# MarazLiteKumanda.net
KiCad netlist of a schematic drawn in EAGLE
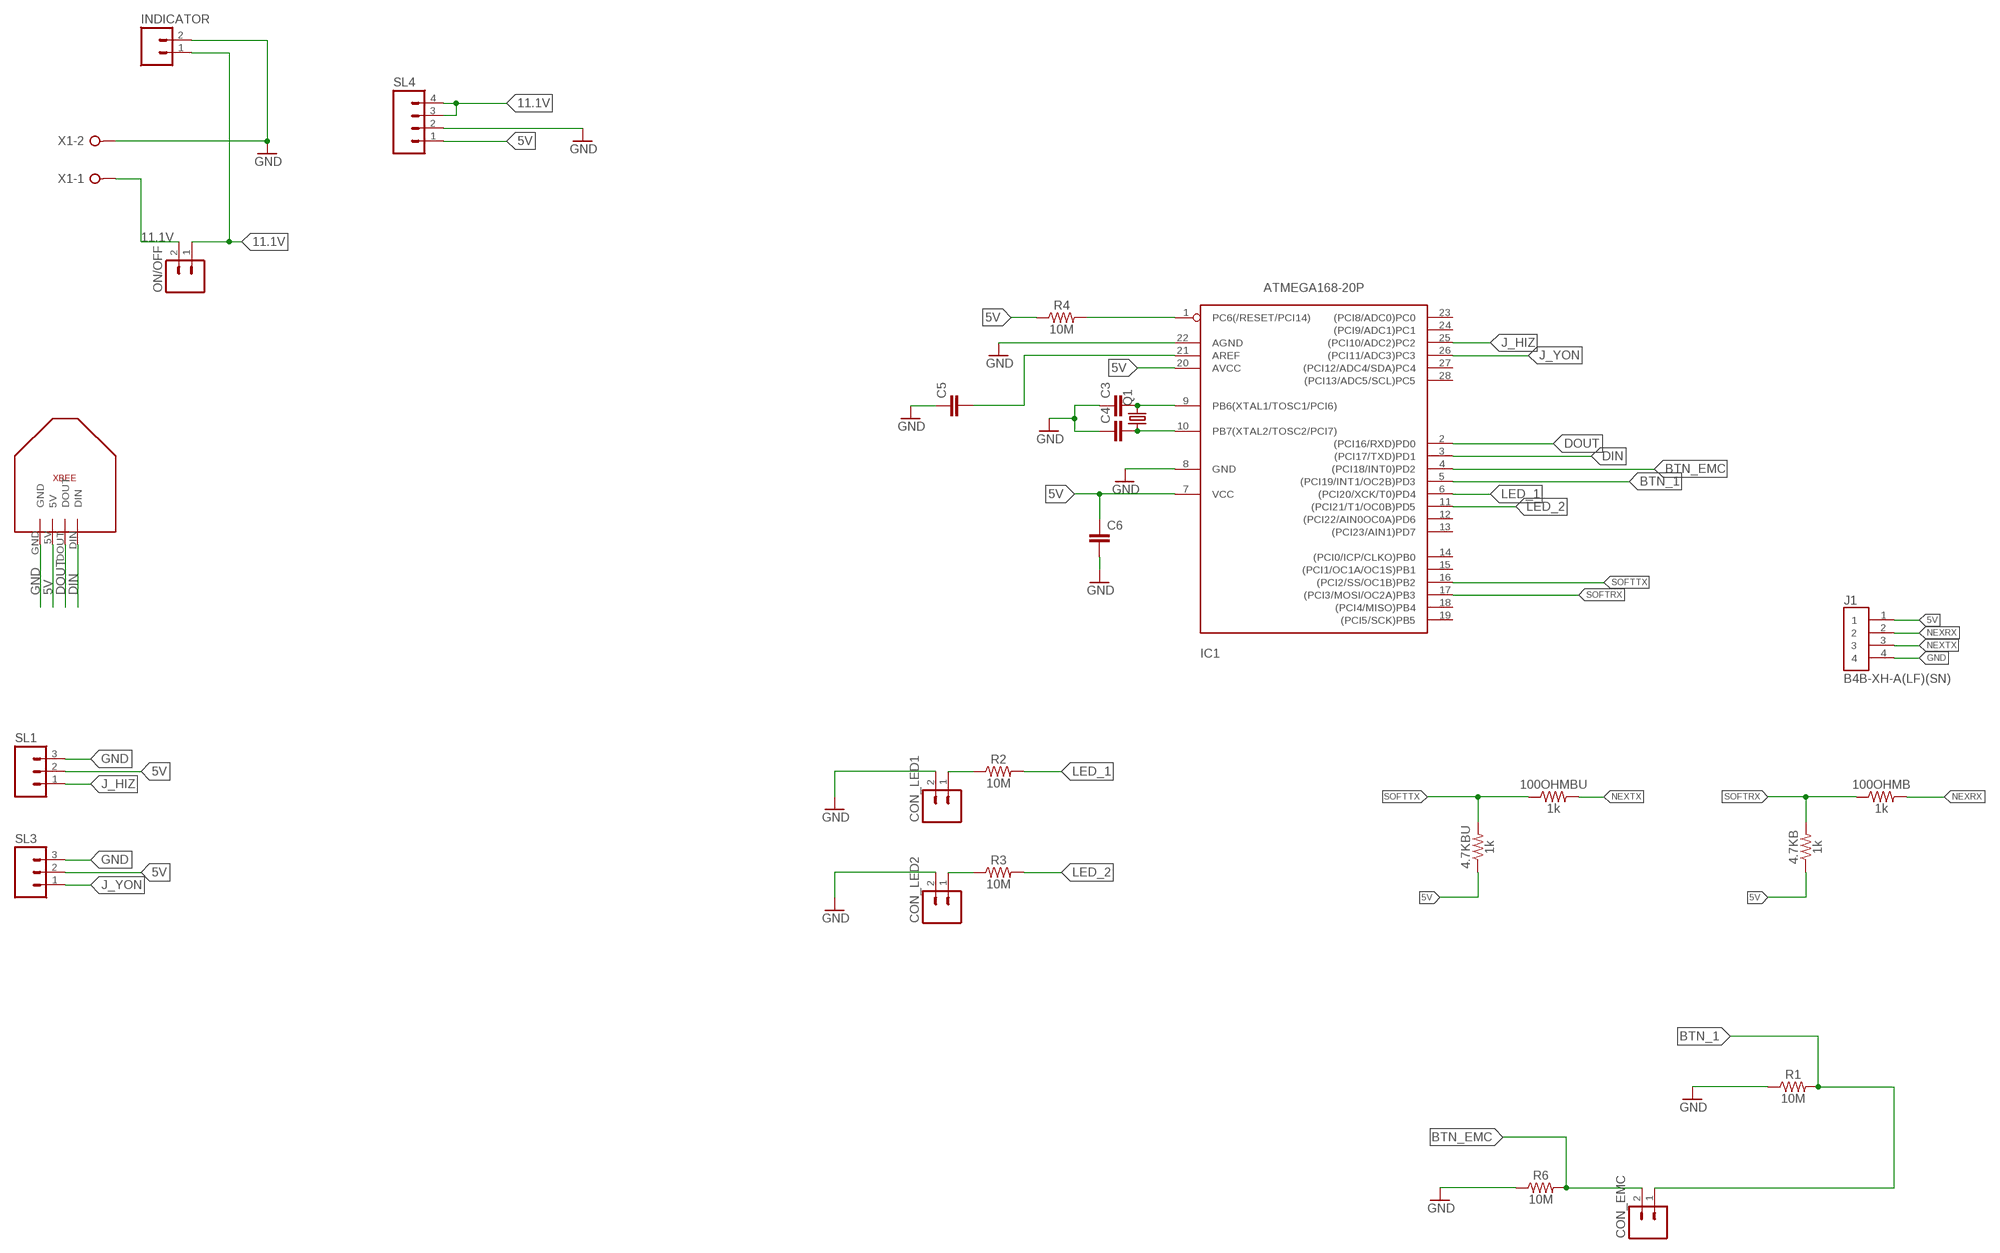
[diagram p0: schematic, sheet 1]

(export (version "E")
  (design (tool "Eeschema 10.0.6"))
  (components
    (comp (ref "4.7KB")
      (value "1k")
      (footprint "eagle-import:AXIAL-0.3")
      (libsource (lib "eagle-import") (part "1KOHM-HORIZ-1/4W-5%"))
    )
    (comp (ref "4.7KBU")
      (value "1k")
      (footprint "eagle-import:AXIAL-0.3")
      (libsource (lib "eagle-import") (part "1KOHM-HORIZ-1/4W-5%"))
    )
    (comp (ref "100OHMB")
      (value "1k")
      (footprint "eagle-import:AXIAL-0.3")
      (libsource (lib "eagle-import") (part "1KOHM-HORIZ-1/4W-5%"))
    )
    (comp (ref "100OHMBU")
      (value "1k")
      (footprint "eagle-import:AXIAL-0.3")
      (libsource (lib "eagle-import") (part "1KOHM-HORIZ-1/4W-5%"))
    )
    (comp (ref "C3")
      (value "C2.5/2")
      (footprint "eagle-import:C2.5-2")
      (libsource (lib "eagle-import") (part "C2.5/2"))
    )
    (comp (ref "C4")
      (value "C2.5/2")
      (footprint "eagle-import:C2.5-2")
      (libsource (lib "eagle-import") (part "C2.5/2"))
    )
    (comp (ref "C5")
      (value "C2.5/2")
      (footprint "eagle-import:C2.5-2")
      (libsource (lib "eagle-import") (part "C2.5/2"))
    )
    (comp (ref "C6")
      (value "C2.5/2")
      (footprint "eagle-import:C2.5-2")
      (libsource (lib "eagle-import") (part "C2.5/2"))
    )
    (comp (ref "CON_EMC")
      (value "M02")
      (footprint "eagle-import:02P")
      (libsource (lib "eagle-import") (part "M02"))
    )
    (comp (ref "CON_LED1")
      (value "M02")
      (footprint "eagle-import:02P")
      (libsource (lib "eagle-import") (part "M02"))
    )
    (comp (ref "CON_LED2")
      (value "M02")
      (footprint "eagle-import:02P")
      (libsource (lib "eagle-import") (part "M02"))
    )
    (comp (ref "IC1")
      (value "ATMEGA168-20P")
      (footprint "eagle-import:DIL28-3")
      (libsource (lib "eagle-import") (part "ATMEGA168P-20"))
    )
    (comp (ref "INDICATOR")
      (value "M02")
      (footprint "eagle-import:02P")
      (libsource (lib "eagle-import") (part "M02"))
    )
    (comp (ref "J1")
      (value "B4B-XH-A(LF)(SN)")
      (footprint "eagle-import:JST_B4B-XH-A(LF)(SN)")
      (fields (field (name "DIGI-KEY_PART_NUMBER") "455-2249-ND") (field (name "MF") "JST Sales"))
      (libsource (lib "eagle-import") (part "B4B-XH-A(LF)(SN)"))
    )
    (comp (ref "ON/OFF")
      (value "M02")
      (footprint "eagle-import:02P")
      (libsource (lib "eagle-import") (part "M02"))
    )
    (comp (ref "Q1")
      (value "CRYSTALHC49U-V")
      (footprint "eagle-import:HC49U-V")
      (libsource (lib "eagle-import") (part "CRYSTALHC49U-V"))
    )
    (comp (ref "R1")
      (value "10M")
      (footprint "eagle-import:AXIAL-0.3")
      (libsource (lib "eagle-import") (part "10MOHM-HORIZ-1/4W-5%"))
    )
    (comp (ref "R2")
      (value "10M")
      (footprint "eagle-import:AXIAL-0.3")
      (libsource (lib "eagle-import") (part "10MOHM-HORIZ-1/4W-5%"))
    )
    (comp (ref "R3")
      (value "10M")
      (footprint "eagle-import:AXIAL-0.3")
      (libsource (lib "eagle-import") (part "10MOHM-HORIZ-1/4W-5%"))
    )
    (comp (ref "R4")
      (value "10M")
      (footprint "eagle-import:AXIAL-0.3")
      (libsource (lib "eagle-import") (part "10MOHM-HORIZ-1/4W-5%"))
    )
    (comp (ref "R6")
      (value "10M")
      (footprint "eagle-import:AXIAL-0.3")
      (libsource (lib "eagle-import") (part "10MOHM-HORIZ-1/4W-5%"))
    )
    (comp (ref "SL1")
      (value "M03")
      (footprint "eagle-import:03P")
      (libsource (lib "eagle-import") (part "M03"))
    )
    (comp (ref "SL3")
      (value "M03")
      (footprint "eagle-import:03P")
      (libsource (lib "eagle-import") (part "M03"))
    )
    (comp (ref "SL4")
      (value "M04")
      (footprint "eagle-import:04P")
      (libsource (lib "eagle-import") (part "M04"))
    )
    (comp (ref "U$1")
      (value "XBEE")
      (footprint "eagle-import:XBEE")
      (libsource (lib "eagle-import") (part "XBEE"))
    )
    (comp (ref "X1")
      (value "W237-02P")
      (footprint "eagle-import:W237-132")
      (libsource (lib "eagle-import") (part "W237-02P"))
    )
  )
  (nets
    (net (code "1") (name "5V") (class "Default")
      (node (ref "4.7KB") (pin "P$1") (pinfunction "1_P$1") (pintype "passive"))
      (node (ref "4.7KBU") (pin "P$1") (pinfunction "1_P$1") (pintype "passive"))
      (node (ref "C6") (pin "1") (pinfunction "1_1") (pintype "passive"))
      (node (ref "IC1") (pin "20") (pinfunction "AVCC_20") (pintype "bidirectional"))
      (node (ref "IC1") (pin "7") (pinfunction "VCC_7") (pintype "bidirectional"))
      (node (ref "J1") (pin "1") (pinfunction "1_1") (pintype "passive"))
      (node (ref "R4") (pin "P$1") (pinfunction "1_P$1") (pintype "passive"))
      (node (ref "SL1") (pin "2") (pinfunction "2_2") (pintype "passive"))
      (node (ref "SL3") (pin "2") (pinfunction "2_2") (pintype "passive"))
      (node (ref "SL4") (pin "1") (pinfunction "1_1") (pintype "passive"))
      (node (ref "U$1") (pin "5V") (pinfunction "5V_5V") (pintype "bidirectional"))
    )
    (net (code "2") (name "11.1V") (class "Default")
      (node (ref "INDICATOR") (pin "1") (pinfunction "1_1") (pintype "passive"))
      (node (ref "ON/OFF") (pin "1") (pinfunction "1_1") (pintype "passive"))
      (node (ref "ON/OFF") (pin "2") (pinfunction "2_2") (pintype "passive"))
      (node (ref "SL4") (pin "3") (pinfunction "3_3") (pintype "passive"))
      (node (ref "SL4") (pin "4") (pinfunction "4_4") (pintype "passive"))
      (node (ref "X1") (pin "1") (pinfunction "KL_1") (pintype "passive"))
    )
    (net (code "3") (name "BTN_1") (class "Default")
      (node (ref "CON_EMC") (pin "1") (pinfunction "1_1") (pintype "passive"))
      (node (ref "IC1") (pin "5") (pinfunction "(PCI19/INT1/OC2B)PD3_5") (pintype "bidirectional"))
      (node (ref "R1") (pin "P$2") (pinfunction "2_P$2") (pintype "passive"))
    )
    (net (code "4") (name "BTN_EMC") (class "Default")
      (node (ref "CON_EMC") (pin "2") (pinfunction "2_2") (pintype "passive"))
      (node (ref "IC1") (pin "4") (pinfunction "(PCI18/INT0)PD2_4") (pintype "bidirectional"))
      (node (ref "R6") (pin "P$2") (pinfunction "2_P$2") (pintype "passive"))
    )
    (net (code "5") (name "DIN") (class "Default")
      (node (ref "IC1") (pin "3") (pinfunction "(PCI17/TXD)PD1_3") (pintype "bidirectional"))
      (node (ref "U$1") (pin "DIN") (pinfunction "DIN_DIN") (pintype "bidirectional"))
    )
    (net (code "6") (name "DOUT") (class "Default")
      (node (ref "IC1") (pin "2") (pinfunction "(PCI16/RXD)PD0_2") (pintype "bidirectional"))
      (node (ref "U$1") (pin "DOUT") (pinfunction "DOUT_DOUT") (pintype "bidirectional"))
    )
    (net (code "7") (name "GND") (class "Default")
      (node (ref "C3") (pin "1") (pinfunction "1_1") (pintype "passive"))
      (node (ref "C4") (pin "1") (pinfunction "1_1") (pintype "passive"))
      (node (ref "C5") (pin "1") (pinfunction "1_1") (pintype "passive"))
      (node (ref "C6") (pin "2") (pinfunction "2_2") (pintype "passive"))
      (node (ref "CON_LED1") (pin "2") (pinfunction "2_2") (pintype "passive"))
      (node (ref "CON_LED2") (pin "2") (pinfunction "2_2") (pintype "passive"))
      (node (ref "IC1") (pin "22") (pinfunction "AGND_22") (pintype "bidirectional"))
      (node (ref "IC1") (pin "8") (pinfunction "GND_8") (pintype "bidirectional"))
      (node (ref "INDICATOR") (pin "2") (pinfunction "2_2") (pintype "passive"))
      (node (ref "J1") (pin "4") (pinfunction "4_4") (pintype "passive"))
      (node (ref "R1") (pin "P$1") (pinfunction "1_P$1") (pintype "passive"))
      (node (ref "R6") (pin "P$1") (pinfunction "1_P$1") (pintype "passive"))
      (node (ref "SL1") (pin "3") (pinfunction "3_3") (pintype "passive"))
      (node (ref "SL3") (pin "3") (pinfunction "3_3") (pintype "passive"))
      (node (ref "SL4") (pin "2") (pinfunction "2_2") (pintype "passive"))
      (node (ref "U$1") (pin "GND") (pinfunction "GND_GND") (pintype "bidirectional"))
      (node (ref "X1") (pin "2") (pinfunction "KL_2") (pintype "passive"))
    )
    (net (code "8") (name "J_HIZ") (class "Default")
      (node (ref "IC1") (pin "25") (pinfunction "(PCI10/ADC2)PC2_25") (pintype "bidirectional"))
      (node (ref "SL1") (pin "1") (pinfunction "1_1") (pintype "passive"))
    )
    (net (code "9") (name "J_YON") (class "Default")
      (node (ref "IC1") (pin "26") (pinfunction "(PCI11/ADC3)PC3_26") (pintype "bidirectional"))
      (node (ref "SL3") (pin "1") (pinfunction "1_1") (pintype "passive"))
    )
    (net (code "10") (name "LED_1") (class "Default")
      (node (ref "IC1") (pin "6") (pinfunction "(PCI20/XCK/T0)PD4_6") (pintype "bidirectional"))
      (node (ref "R2") (pin "P$2") (pinfunction "2_P$2") (pintype "passive"))
    )
    (net (code "11") (name "LED_2") (class "Default")
      (node (ref "IC1") (pin "11") (pinfunction "(PCI21/T1/OC0B)PD5_11") (pintype "bidirectional"))
      (node (ref "R3") (pin "P$2") (pinfunction "2_P$2") (pintype "passive"))
    )
    (net (code "12") (name "NEXRX") (class "Default")
      (node (ref "100OHMB") (pin "P$2") (pinfunction "2_P$2") (pintype "passive"))
      (node (ref "J1") (pin "2") (pinfunction "2_2") (pintype "passive"))
    )
    (net (code "13") (name "NEXTX") (class "Default")
      (node (ref "100OHMBU") (pin "P$2") (pinfunction "2_P$2") (pintype "passive"))
      (node (ref "J1") (pin "3") (pinfunction "3_3") (pintype "passive"))
    )
    (net (code "14") (name "Net-(IC1-AREF)") (class "Default")
      (node (ref "C5") (pin "2") (pinfunction "2_2") (pintype "passive"))
      (node (ref "IC1") (pin "21") (pinfunction "AREF_21") (pintype "bidirectional"))
    )
    (net (code "15") (name "Net-(IC1-PB6(XTAL1{slash}TOSC1{slash}PCI6))") (class "Default")
      (node (ref "C3") (pin "2") (pinfunction "2_2") (pintype "passive"))
      (node (ref "IC1") (pin "9") (pinfunction "PB6(XTAL1/TOSC1/PCI6)_9") (pintype "bidirectional"))
      (node (ref "Q1") (pin "2") (pinfunction "2_2") (pintype "passive"))
    )
    (net (code "16") (name "Net-(IC1-PB7(XTAL2{slash}TOSC2{slash}PCI7))") (class "Default")
      (node (ref "C4") (pin "2") (pinfunction "2_2") (pintype "passive"))
      (node (ref "IC1") (pin "10") (pinfunction "PB7(XTAL2/TOSC2/PCI7)_10") (pintype "bidirectional"))
      (node (ref "Q1") (pin "1") (pinfunction "1_1") (pintype "passive"))
    )
    (net (code "17") (name "Net-(IC1-PC6({slash}RESET{slash}PCI14))") (class "Default")
      (node (ref "IC1") (pin "1") (pinfunction "PC6(/RESET/PCI14)_1") (pintype "bidirectional"))
      (node (ref "R4") (pin "P$2") (pinfunction "2_P$2") (pintype "passive"))
    )
    (net (code "18") (name "Net-(R2-1)") (class "Default")
      (node (ref "CON_LED1") (pin "1") (pinfunction "1_1") (pintype "passive"))
      (node (ref "R2") (pin "P$1") (pinfunction "1_P$1") (pintype "passive"))
    )
    (net (code "19") (name "Net-(R3-1)") (class "Default")
      (node (ref "CON_LED2") (pin "1") (pinfunction "1_1") (pintype "passive"))
      (node (ref "R3") (pin "P$1") (pinfunction "1_P$1") (pintype "passive"))
    )
    (net (code "20") (name "SOFTRX") (class "Default")
      (node (ref "100OHMB") (pin "P$1") (pinfunction "1_P$1") (pintype "passive"))
      (node (ref "4.7KB") (pin "P$2") (pinfunction "2_P$2") (pintype "passive"))
      (node (ref "IC1") (pin "17") (pinfunction "(PCI3/MOSI/OC2A)PB3_17") (pintype "bidirectional"))
    )
    (net (code "21") (name "SOFTTX") (class "Default")
      (node (ref "100OHMBU") (pin "P$1") (pinfunction "1_P$1") (pintype "passive"))
      (node (ref "4.7KBU") (pin "P$2") (pinfunction "2_P$2") (pintype "passive"))
      (node (ref "IC1") (pin "16") (pinfunction "(PCI2/SS/OC1B)PB2_16") (pintype "bidirectional"))
    )
    (net (code "22") (name "unconnected-(IC1-(PCI0{slash}ICP{slash}CLKO)PB0-Pad14)") (class "Default")
      (node (ref "IC1") (pin "14") (pinfunction "(PCI0/ICP/CLKO)PB0_14") (pintype "bidirectional"))
    )
    (net (code "23") (name "unconnected-(IC1-(PCI1{slash}OC1A{slash}OC1S)PB1-Pad15)") (class "Default")
      (node (ref "IC1") (pin "15") (pinfunction "(PCI1/OC1A/OC1S)PB1_15") (pintype "bidirectional"))
    )
    (net (code "24") (name "unconnected-(IC1-(PCI4{slash}MISO)PB4-Pad18)") (class "Default")
      (node (ref "IC1") (pin "18") (pinfunction "(PCI4/MISO)PB4_18") (pintype "bidirectional"))
    )
    (net (code "25") (name "unconnected-(IC1-(PCI5{slash}SCK)PB5-Pad19)") (class "Default")
      (node (ref "IC1") (pin "19") (pinfunction "(PCI5/SCK)PB5_19") (pintype "bidirectional"))
    )
    (net (code "26") (name "unconnected-(IC1-(PCI8{slash}ADC0)PC0-Pad23)") (class "Default")
      (node (ref "IC1") (pin "23") (pinfunction "(PCI8/ADC0)PC0_23") (pintype "bidirectional"))
    )
    (net (code "27") (name "unconnected-(IC1-(PCI9{slash}ADC1)PC1-Pad24)") (class "Default")
      (node (ref "IC1") (pin "24") (pinfunction "(PCI9/ADC1)PC1_24") (pintype "bidirectional"))
    )
    (net (code "28") (name "unconnected-(IC1-(PCI12{slash}ADC4{slash}SDA)PC4-Pad27)") (class "Default")
      (node (ref "IC1") (pin "27") (pinfunction "(PCI12/ADC4/SDA)PC4_27") (pintype "bidirectional"))
    )
    (net (code "29") (name "unconnected-(IC1-(PCI13{slash}ADC5{slash}SCL)PC5-Pad28)") (class "Default")
      (node (ref "IC1") (pin "28") (pinfunction "(PCI13/ADC5/SCL)PC5_28") (pintype "bidirectional"))
    )
    (net (code "30") (name "unconnected-(IC1-(PCI22{slash}AIN0OC0A)PD6-Pad12)") (class "Default")
      (node (ref "IC1") (pin "12") (pinfunction "(PCI22/AIN0OC0A)PD6_12") (pintype "bidirectional"))
    )
    (net (code "31") (name "unconnected-(IC1-(PCI23{slash}AIN1)PD7-Pad13)") (class "Default")
      (node (ref "IC1") (pin "13") (pinfunction "(PCI23/AIN1)PD7_13") (pintype "bidirectional"))
    )
  )
)
